# POWER.net
KiCad netlist of a schematic drawn in Altium Designer
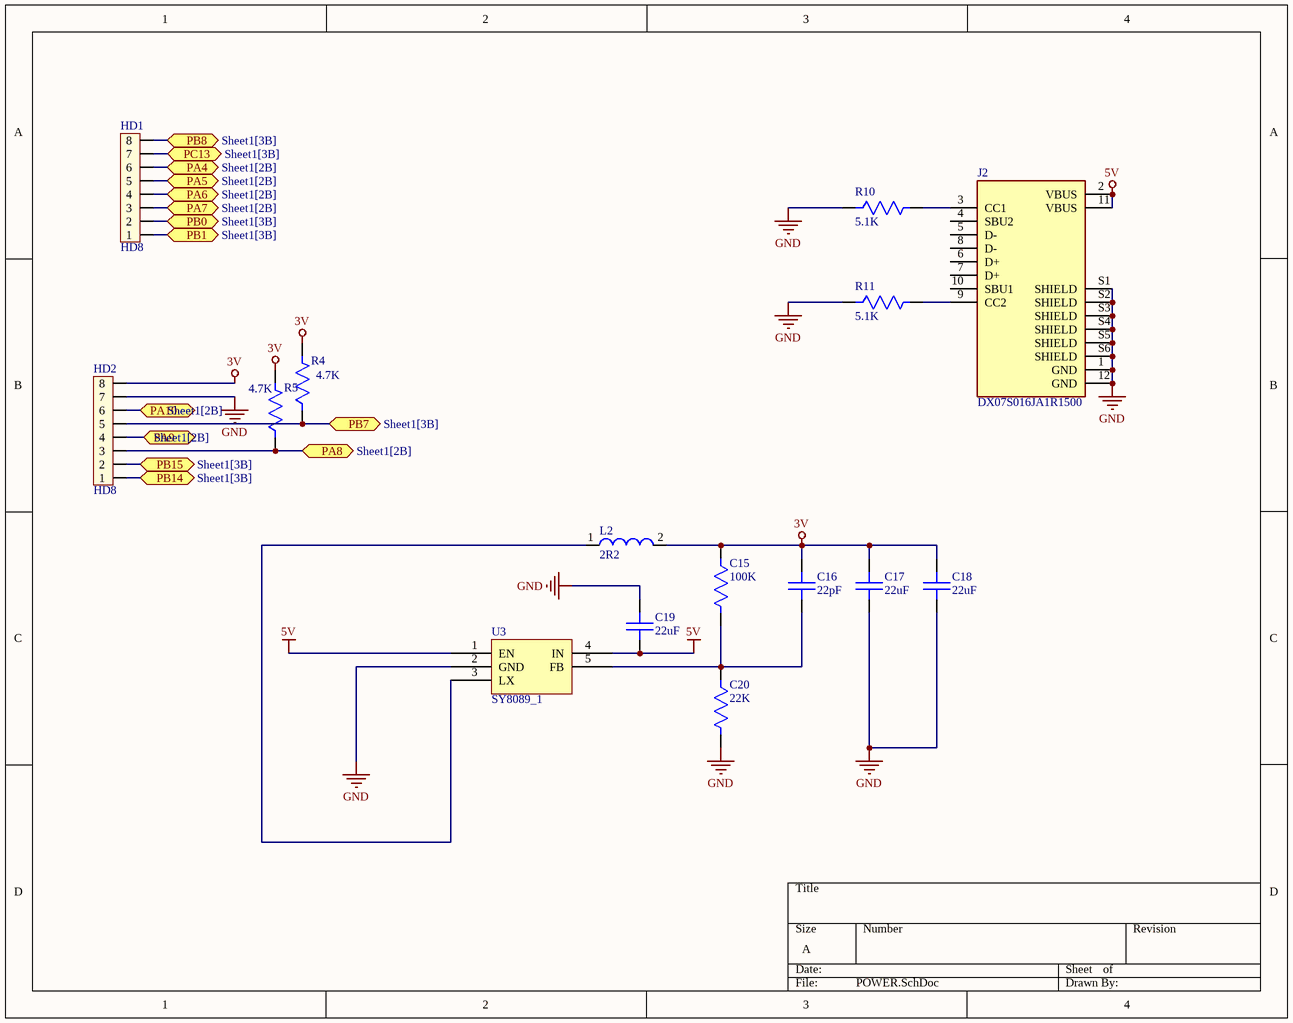
[diagram p0: POWER.SchDoc]

(export (version "E")
  (design (tool "Eeschema 10.0.6"))
  (components
    (comp (ref "C15")
      (value "100K")
      (footprint "R0603")
      (description "SMD Resistor 0603")
      (fields
        (field (name "MANUFACTURER") "Yageo")
        (field (name "MANUFACTURER PART NUMBER") "RC0603FR-071KL")
      )
      (libsource (lib "DAT_Schlib") (part "Resistor 0603"))
    )
    (comp (ref "C16")
      (value "22pF")
      (footprint "C0603")
      (libsource (lib "DAT_Schlib") (part "Capacitor 0603"))
    )
    (comp (ref "C17")
      (value "22uF")
      (footprint "C0603")
      (libsource (lib "DAT_Schlib") (part "Capacitor 0603"))
    )
    (comp (ref "C18")
      (value "22uF")
      (footprint "C0603")
      (libsource (lib "DAT_Schlib") (part "Capacitor 0603"))
    )
    (comp (ref "C19")
      (value "22uF")
      (footprint "C0603")
      (libsource (lib "DAT_Schlib") (part "Capacitor 0603"))
    )
    (comp (ref "C20")
      (value "22K")
      (footprint "R0603")
      (description "SMD Resistor 0603")
      (fields
        (field (name "MANUFACTURER") "Yageo")
        (field (name "MANUFACTURER PART NUMBER") "RC0603FR-071KL")
      )
      (libsource (lib "DAT_Schlib") (part "Resistor 0603"))
    )
    (comp (ref "HD1")
      (value "HD8")
      (footprint "Header_8")
      (description "Header 8")
      (fields (field (name "CREAT BY") "VanDungEvn@Gmail.com"))
      (libsource (lib "LPSON") (part "Header8"))
    )
    (comp (ref "HD2")
      (value "HD8")
      (footprint "Header_8")
      (description "Header 8")
      (fields (field (name "CREAT BY") "VanDungEvn@Gmail.com"))
      (libsource (lib "LPSON") (part "Header8"))
    )
    (comp (ref "J2")
      (value "DX07S016JA1R1500")
      (footprint "JAE_DX07S016JA1R1500")
      (libsource (lib "DX07S016JA1R1500") (part "DX07S016JA1R1500"))
    )
    (comp (ref "L2")
      (value "2R2")
      (footprint "L0630")
      (description "HIGH POWER INDUCTOR 1040")
      (fields (field (name "MF") "Wurth Electronics") (field (name "MP") "74437368047"))
      (libsource (lib "UY_Schlib") (part "Inductor 0630"))
    )
    (comp (ref "R4")
      (value "4.7K")
      (footprint "R0603")
      (description "SMD Resistor 0603")
      (fields
        (field (name "MANUFACTURER") "Yageo")
        (field (name "MANUFACTURER PART NUMBER") "RC0603FR-071KL")
      )
      (libsource (lib "IoTVision_Library") (part "Resistor 0603"))
    )
    (comp (ref "R5")
      (value "4.7K")
      (footprint "R0603")
      (description "SMD Resistor 0603")
      (fields
        (field (name "MANUFACTURER") "Yageo")
        (field (name "MANUFACTURER PART NUMBER") "RC0603FR-071KL")
      )
      (libsource (lib "IoTVision_Library") (part "Resistor 0603"))
    )
    (comp (ref "R10")
      (value "5.1K")
      (footprint "R0603")
      (description "SMD Resistor 0603")
      (fields
        (field (name "MANUFACTURER") "Yageo")
        (field (name "MANUFACTURER PART NUMBER") "RC0603FR-071KL")
      )
      (libsource (lib "Tram_muoi_VietAn") (part "Resistor 0603"))
    )
    (comp (ref "R11")
      (value "5.1K")
      (footprint "R0603")
      (description "SMD Resistor 0603")
      (fields
        (field (name "MANUFACTURER") "Yageo")
        (field (name "MANUFACTURER PART NUMBER") "RC0603FR-071KL")
      )
      (libsource (lib "Tram_muoi_VietAn") (part "Resistor 0603"))
    )
    (comp (ref "U3") (value "SY8089_1") (footprint "SOT23-5") (libsource (lib "My_lib") (part "SY8089_1")))
  )
  (nets
    (net (code "1") (name "/PA4") (class "Default")
      (node (ref "HD1") (pin "6") (pinfunction "6_6") (pintype "passive"))
    )
    (net (code "2") (name "/PA5") (class "Default")
      (node (ref "HD1") (pin "5") (pinfunction "5_5") (pintype "passive"))
    )
    (net (code "3") (name "/PA6") (class "Default")
      (node (ref "HD1") (pin "4") (pinfunction "4_4") (pintype "passive"))
    )
    (net (code "4") (name "/PA7") (class "Default")
      (node (ref "HD1") (pin "3") (pinfunction "3_3") (pintype "passive"))
    )
    (net (code "5") (name "/PA8") (class "Default")
      (node (ref "HD2") (pin "3") (pinfunction "3_3") (pintype "passive"))
      (node (ref "R5") (pin "1") (pinfunction "1_1") (pintype "passive"))
    )
    (net (code "6") (name "/PA9") (class "Default")
      (node (ref "HD2") (pin "4") (pinfunction "4_4") (pintype "passive"))
    )
    (net (code "7") (name "/PA10") (class "Default")
      (node (ref "HD2") (pin "6") (pinfunction "6_6") (pintype "passive"))
    )
    (net (code "8") (name "/PB0") (class "Default")
      (node (ref "HD1") (pin "2") (pinfunction "2_2") (pintype "passive"))
    )
    (net (code "9") (name "/PB1") (class "Default")
      (node (ref "HD1") (pin "1") (pinfunction "1_1") (pintype "passive"))
    )
    (net (code "10") (name "/PB7") (class "Default")
      (node (ref "HD2") (pin "5") (pinfunction "5_5") (pintype "passive"))
      (node (ref "R4") (pin "1") (pinfunction "1_1") (pintype "passive"))
    )
    (net (code "11") (name "/PB8") (class "Default")
      (node (ref "HD1") (pin "8") (pinfunction "8_8") (pintype "passive"))
    )
    (net (code "12") (name "/PB14") (class "Default")
      (node (ref "HD2") (pin "1") (pinfunction "1_1") (pintype "passive"))
    )
    (net (code "13") (name "/PB15") (class "Default")
      (node (ref "HD2") (pin "2") (pinfunction "2_2") (pintype "passive"))
    )
    (net (code "14") (name "/PC13") (class "Default")
      (node (ref "HD1") (pin "7") (pinfunction "7_7") (pintype "passive"))
    )
    (net (code "15") (name "3V") (class "Default")
      (node (ref "C15") (pin "1") (pinfunction "1_1") (pintype "passive"))
      (node (ref "C16") (pin "2") (pinfunction "2_2") (pintype "passive"))
      (node (ref "C17") (pin "2") (pinfunction "2_2") (pintype "passive"))
      (node (ref "C18") (pin "2") (pinfunction "2_2") (pintype "passive"))
      (node (ref "HD2") (pin "8") (pinfunction "8_8") (pintype "passive"))
      (node (ref "L2") (pin "2") (pinfunction "2_2") (pintype "passive"))
      (node (ref "R4") (pin "2") (pinfunction "2_2") (pintype "passive"))
      (node (ref "R5") (pin "2") (pinfunction "2_2") (pintype "passive"))
    )
    (net (code "16") (name "5V") (class "Default")
      (node (ref "C19") (pin "2") (pinfunction "2_2") (pintype "passive"))
      (node (ref "J2") (pin "11") (pinfunction "VBUS_11") (pintype "power_in"))
      (node (ref "J2") (pin "2") (pinfunction "VBUS_2") (pintype "power_in"))
      (node (ref "U3") (pin "1") (pinfunction "EN_1") (pintype "passive"))
      (node (ref "U3") (pin "4") (pinfunction "IN_4") (pintype "passive"))
    )
    (net (code "17") (name "GND") (class "Default")
      (node (ref "C17") (pin "1") (pinfunction "1_1") (pintype "passive"))
      (node (ref "C18") (pin "1") (pinfunction "1_1") (pintype "passive"))
      (node (ref "C19") (pin "1") (pinfunction "1_1") (pintype "passive"))
      (node (ref "C20") (pin "2") (pinfunction "2_2") (pintype "passive"))
      (node (ref "HD2") (pin "7") (pinfunction "7_7") (pintype "passive"))
      (node (ref "J2") (pin "1") (pinfunction "GND_1") (pintype "power_in"))
      (node (ref "J2") (pin "12") (pinfunction "GND_12") (pintype "power_in"))
      (node (ref "J2") (pin "S1") (pinfunction "SHIELD_S1") (pintype "passive"))
      (node (ref "J2") (pin "S2") (pinfunction "SHIELD_S2") (pintype "passive"))
      (node (ref "J2") (pin "S3") (pinfunction "SHIELD_S3") (pintype "passive"))
      (node (ref "J2") (pin "S4") (pinfunction "SHIELD_S4") (pintype "passive"))
      (node (ref "J2") (pin "S5") (pinfunction "SHIELD_S5") (pintype "passive"))
      (node (ref "J2") (pin "S6") (pinfunction "SHIELD_S6") (pintype "passive"))
      (node (ref "R10") (pin "1") (pinfunction "1_1") (pintype "passive"))
      (node (ref "R11") (pin "1") (pinfunction "1_1") (pintype "passive"))
      (node (ref "U3") (pin "2") (pinfunction "GND_2") (pintype "passive"))
    )
    (net (code "18") (name "Net-(J2-CC1)") (class "Default")
      (node (ref "J2") (pin "3") (pinfunction "CC1_3") (pintype "passive"))
      (node (ref "R10") (pin "2") (pinfunction "2_2") (pintype "passive"))
    )
    (net (code "19") (name "Net-(J2-CC2)") (class "Default")
      (node (ref "J2") (pin "9") (pinfunction "CC2_9") (pintype "passive"))
      (node (ref "R11") (pin "2") (pinfunction "2_2") (pintype "passive"))
    )
    (net (code "20") (name "Net-(U3-FB)") (class "Default")
      (node (ref "C15") (pin "2") (pinfunction "2_2") (pintype "passive"))
      (node (ref "C16") (pin "1") (pinfunction "1_1") (pintype "passive"))
      (node (ref "C20") (pin "1") (pinfunction "1_1") (pintype "passive"))
      (node (ref "U3") (pin "5") (pinfunction "FB_5") (pintype "passive"))
    )
    (net (code "21") (name "Net-(U3-LX)") (class "Default")
      (node (ref "L2") (pin "1") (pinfunction "1_1") (pintype "passive"))
      (node (ref "U3") (pin "3") (pinfunction "LX_3") (pintype "passive"))
    )
    (net (code "22") (name "unconnected-(J2-D+-Pad6)") (class "Default")
      (node (ref "J2") (pin "6") (pinfunction "D+_6") (pintype "passive"))
    )
    (net (code "23") (name "unconnected-(J2-D+-Pad7)") (class "Default")
      (node (ref "J2") (pin "7") (pinfunction "D+_7") (pintype "passive"))
    )
    (net (code "24") (name "unconnected-(J2-D--Pad5)") (class "Default")
      (node (ref "J2") (pin "5") (pinfunction "D-_5") (pintype "passive"))
    )
    (net (code "25") (name "unconnected-(J2-D--Pad8)") (class "Default")
      (node (ref "J2") (pin "8") (pinfunction "D-_8") (pintype "passive"))
    )
    (net (code "26") (name "unconnected-(J2-SBU1-Pad10)") (class "Default")
      (node (ref "J2") (pin "10") (pinfunction "SBU1_10") (pintype "passive"))
    )
    (net (code "27") (name "unconnected-(J2-SBU2-Pad4)") (class "Default")
      (node (ref "J2") (pin "4") (pinfunction "SBU2_4") (pintype "passive"))
    )
  )
)
